# divchrono-aux.net
KiCad netlist of a schematic drawn in EAGLE
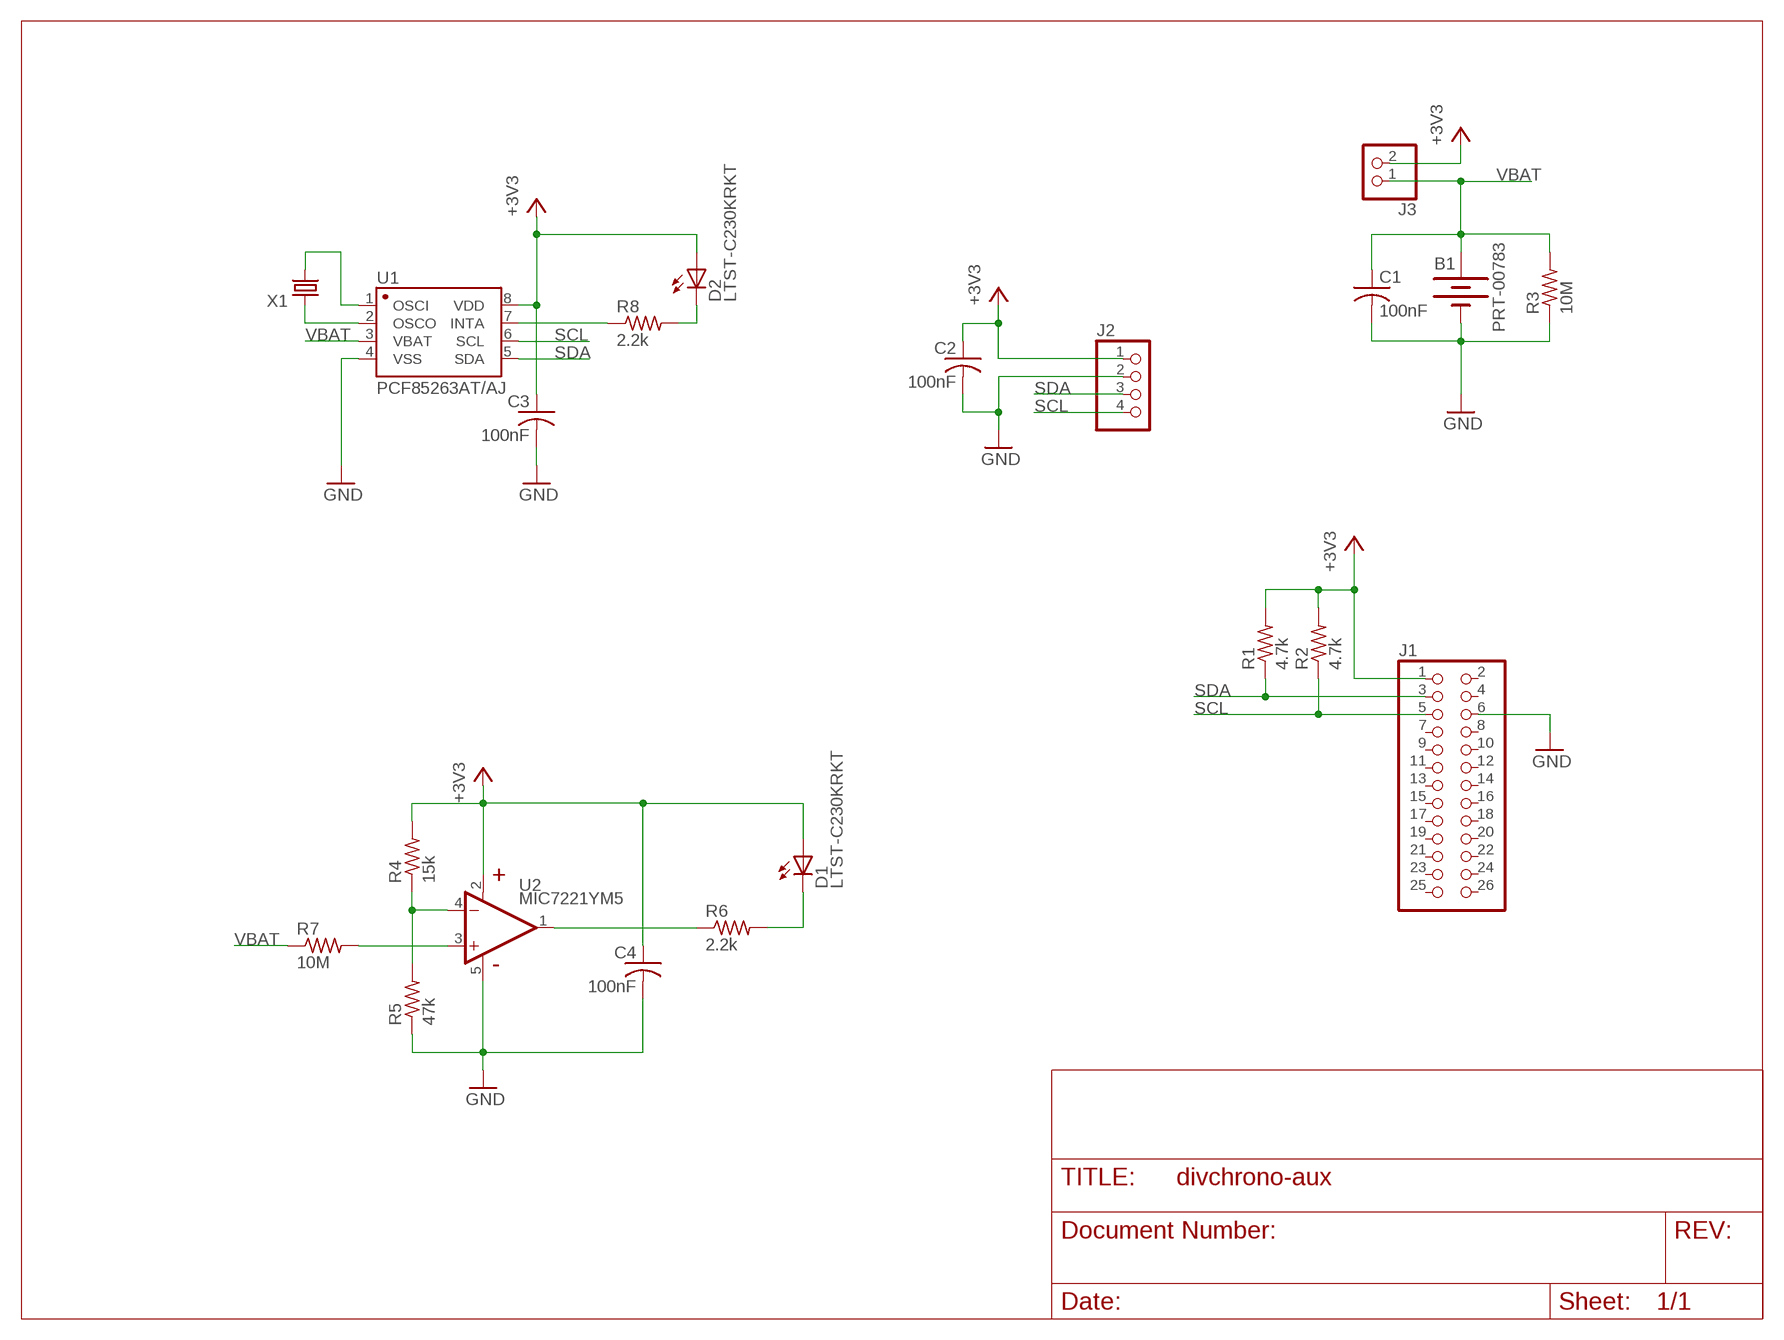
[diagram p0: schematic, sheet 1]

(export (version "E")
  (design (tool "Eeschema 10.0.6"))
  (components
    (comp (ref "B1")
      (value "PRT-00783")
      (footprint "eagle-import:BATTCOM_20MM_PTH")
      (libsource (lib "eagle-import") (part "BATTERY20PTH"))
    )
    (comp (ref "C1")
      (value "100nF")
      (footprint "eagle-import:C1206")
      (libsource (lib "eagle-import") (part "C-USC1206"))
    )
    (comp (ref "C2")
      (value "100nF")
      (footprint "eagle-import:C1206")
      (libsource (lib "eagle-import") (part "C-USC1206"))
    )
    (comp (ref "C3")
      (value "100nF")
      (footprint "eagle-import:C1206")
      (libsource (lib "eagle-import") (part "C-USC1206"))
    )
    (comp (ref "C4")
      (value "100nF")
      (footprint "eagle-import:C1206")
      (libsource (lib "eagle-import") (part "C-USC1206"))
    )
    (comp (ref "D1")
      (value "LTST-C230KRKT")
      (footprint "eagle-import:CHIPLED_1206")
      (libsource (lib "eagle-import") (part "LEDCHIPLED_1206"))
    )
    (comp (ref "D2")
      (value "LTST-C230KRKT")
      (footprint "eagle-import:CHIPLED_1206")
      (libsource (lib "eagle-import") (part "LEDCHIPLED_1206"))
    )
    (comp (ref "J1")
      (value "PINHD-2X13")
      (footprint "eagle-import:2X13")
      (libsource (lib "eagle-import") (part "PINHD-2X13"))
    )
    (comp (ref "J2")
      (value "PINHD-1X4")
      (footprint "eagle-import:1X04")
      (libsource (lib "eagle-import") (part "PINHD-1X4"))
    )
    (comp (ref "J3")
      (value "PINHD-1X2")
      (footprint "eagle-import:1X02")
      (libsource (lib "eagle-import") (part "PINHD-1X2"))
    )
    (comp (ref "R1")
      (value "4.7k")
      (footprint "eagle-import:R1206")
      (libsource (lib "eagle-import") (part "R-US_R1206"))
    )
    (comp (ref "R2")
      (value "4.7k")
      (footprint "eagle-import:R1206")
      (libsource (lib "eagle-import") (part "R-US_R1206"))
    )
    (comp (ref "R3")
      (value "10M")
      (footprint "eagle-import:R1206")
      (libsource (lib "eagle-import") (part "R-US_R1206"))
    )
    (comp (ref "R4")
      (value "15k")
      (footprint "eagle-import:R1206")
      (libsource (lib "eagle-import") (part "R-US_R1206"))
    )
    (comp (ref "R5")
      (value "47k")
      (footprint "eagle-import:R1206")
      (libsource (lib "eagle-import") (part "R-US_R1206"))
    )
    (comp (ref "R6")
      (value "2.2k")
      (footprint "eagle-import:R1206")
      (libsource (lib "eagle-import") (part "R-US_R1206"))
    )
    (comp (ref "R7")
      (value "10M")
      (footprint "eagle-import:R1206")
      (libsource (lib "eagle-import") (part "R-US_R1206"))
    )
    (comp (ref "R8")
      (value "2.2k")
      (footprint "eagle-import:R1206")
      (libsource (lib "eagle-import") (part "R-US_R1206"))
    )
    (comp (ref "U1")
      (value "PCF85263AT/AJ")
      (footprint "eagle-import:SOIC-8")
      (libsource (lib "eagle-import") (part "PCF85263"))
    )
    (comp (ref "U2")
      (value "MIC7221YM5")
      (footprint "eagle-import:SOT23-5")
      (libsource (lib "eagle-import") (part "MIC7221YM5"))
    )
    (comp (ref "X1")
      (value "CRYSTALS-NOGND-WATCH-3X8")
      (footprint "eagle-import:WATCH-3X8")
      (libsource (lib "eagle-import") (part "CRYSTALS-NOGND-WATCH-3X8"))
    )
  )
  (nets
    (net (code "1") (name "+3V3") (class "Default")
      (node (ref "C2") (pin "1") (pinfunction "1_1") (pintype "passive"))
      (node (ref "C3") (pin "1") (pinfunction "1_1") (pintype "passive"))
      (node (ref "C4") (pin "1") (pinfunction "1_1") (pintype "passive"))
      (node (ref "D1") (pin "A") (pinfunction "A_A") (pintype "passive"))
      (node (ref "D2") (pin "A") (pinfunction "A_A") (pintype "passive"))
      (node (ref "J1") (pin "1") (pinfunction "1_1") (pintype "passive"))
      (node (ref "J2") (pin "1") (pinfunction "1_1") (pintype "passive"))
      (node (ref "J3") (pin "2") (pinfunction "2_2") (pintype "passive"))
      (node (ref "R1") (pin "2") (pinfunction "2_2") (pintype "passive"))
      (node (ref "R2") (pin "2") (pinfunction "2_2") (pintype "passive"))
      (node (ref "R4") (pin "2") (pinfunction "2_2") (pintype "passive"))
      (node (ref "U1") (pin "8") (pinfunction "VDD_8") (pintype "power_in"))
      (node (ref "U2") (pin "2") (pinfunction "V+_2") (pintype "power_in"))
    )
    (net (code "2") (name "/SCL") (class "Default")
      (node (ref "J1") (pin "5") (pinfunction "5_5") (pintype "passive"))
      (node (ref "J2") (pin "4") (pinfunction "4_4") (pintype "passive"))
      (node (ref "R2") (pin "1") (pinfunction "1_1") (pintype "passive"))
      (node (ref "U1") (pin "6") (pinfunction "SCL_6") (pintype "bidirectional"))
    )
    (net (code "3") (name "/SDA") (class "Default")
      (node (ref "J1") (pin "3") (pinfunction "3_3") (pintype "passive"))
      (node (ref "J2") (pin "3") (pinfunction "3_3") (pintype "passive"))
      (node (ref "R1") (pin "1") (pinfunction "1_1") (pintype "passive"))
      (node (ref "U1") (pin "5") (pinfunction "SDA_5") (pintype "bidirectional"))
    )
    (net (code "4") (name "/VBAT") (class "Default")
      (node (ref "B1") (pin "1") (pinfunction "+_1") (pintype "power_in"))
      (node (ref "C1") (pin "1") (pinfunction "1_1") (pintype "passive"))
      (node (ref "J3") (pin "1") (pinfunction "1_1") (pintype "passive"))
      (node (ref "R3") (pin "2") (pinfunction "2_2") (pintype "passive"))
      (node (ref "R7") (pin "1") (pinfunction "1_1") (pintype "passive"))
      (node (ref "U1") (pin "3") (pinfunction "VBAT_3") (pintype "power_in"))
    )
    (net (code "5") (name "GND") (class "Default")
      (node (ref "B1") (pin "2") (pinfunction "-_2") (pintype "power_in"))
      (node (ref "C1") (pin "2") (pinfunction "2_2") (pintype "passive"))
      (node (ref "C2") (pin "2") (pinfunction "2_2") (pintype "passive"))
      (node (ref "C3") (pin "2") (pinfunction "2_2") (pintype "passive"))
      (node (ref "C4") (pin "2") (pinfunction "2_2") (pintype "passive"))
      (node (ref "J1") (pin "6") (pinfunction "6_6") (pintype "passive"))
      (node (ref "J2") (pin "2") (pinfunction "2_2") (pintype "passive"))
      (node (ref "R3") (pin "1") (pinfunction "1_1") (pintype "passive"))
      (node (ref "R5") (pin "1") (pinfunction "1_1") (pintype "passive"))
      (node (ref "U1") (pin "4") (pinfunction "VSS_4") (pintype "power_in"))
      (node (ref "U2") (pin "5") (pinfunction "V-_5") (pintype "power_in"))
    )
    (net (code "6") (name "Net-(D1-PadC)") (class "Default")
      (node (ref "D1") (pin "C") (pinfunction "C_C") (pintype "passive"))
      (node (ref "R6") (pin "2") (pinfunction "2_2") (pintype "passive"))
    )
    (net (code "7") (name "Net-(D2-PadC)") (class "Default")
      (node (ref "D2") (pin "C") (pinfunction "C_C") (pintype "passive"))
      (node (ref "R8") (pin "2") (pinfunction "2_2") (pintype "passive"))
    )
    (net (code "8") (name "Net-(U1-INTA)") (class "Default")
      (node (ref "R8") (pin "1") (pinfunction "1_1") (pintype "passive"))
      (node (ref "U1") (pin "7") (pinfunction "INTA_7") (pintype "bidirectional"))
    )
    (net (code "9") (name "Net-(U1-OSCI)") (class "Default")
      (node (ref "U1") (pin "1") (pinfunction "OSCI_1") (pintype "bidirectional"))
      (node (ref "X1") (pin "2") (pinfunction "2_2") (pintype "passive"))
    )
    (net (code "10") (name "Net-(U1-OSCO)") (class "Default")
      (node (ref "U1") (pin "2") (pinfunction "OSCO_2") (pintype "bidirectional"))
      (node (ref "X1") (pin "1") (pinfunction "1_1") (pintype "passive"))
    )
    (net (code "11") (name "Net-(U2-+IN)") (class "Default")
      (node (ref "R7") (pin "2") (pinfunction "2_2") (pintype "passive"))
      (node (ref "U2") (pin "3") (pinfunction "+IN_3") (pintype "input"))
    )
    (net (code "12") (name "Net-(U2--IN)") (class "Default")
      (node (ref "R4") (pin "1") (pinfunction "1_1") (pintype "passive"))
      (node (ref "R5") (pin "2") (pinfunction "2_2") (pintype "passive"))
      (node (ref "U2") (pin "4") (pinfunction "-IN_4") (pintype "input"))
    )
    (net (code "13") (name "Net-(U2-OUT)") (class "Default")
      (node (ref "R6") (pin "1") (pinfunction "1_1") (pintype "passive"))
      (node (ref "U2") (pin "1") (pinfunction "OUT_1") (pintype "output"))
    )
    (net (code "14") (name "unconnected-(J1-Pad2)") (class "Default")
      (node (ref "J1") (pin "2") (pinfunction "2_2") (pintype "passive"))
    )
    (net (code "15") (name "unconnected-(J1-Pad4)") (class "Default")
      (node (ref "J1") (pin "4") (pinfunction "4_4") (pintype "passive"))
    )
    (net (code "16") (name "unconnected-(J1-Pad7)") (class "Default")
      (node (ref "J1") (pin "7") (pinfunction "7_7") (pintype "passive"))
    )
    (net (code "17") (name "unconnected-(J1-Pad8)") (class "Default")
      (node (ref "J1") (pin "8") (pinfunction "8_8") (pintype "passive"))
    )
    (net (code "18") (name "unconnected-(J1-Pad9)") (class "Default")
      (node (ref "J1") (pin "9") (pinfunction "9_9") (pintype "passive"))
    )
    (net (code "19") (name "unconnected-(J1-Pad10)") (class "Default")
      (node (ref "J1") (pin "10") (pinfunction "10_10") (pintype "passive"))
    )
    (net (code "20") (name "unconnected-(J1-Pad11)") (class "Default")
      (node (ref "J1") (pin "11") (pinfunction "11_11") (pintype "passive"))
    )
    (net (code "21") (name "unconnected-(J1-Pad12)") (class "Default")
      (node (ref "J1") (pin "12") (pinfunction "12_12") (pintype "passive"))
    )
    (net (code "22") (name "unconnected-(J1-Pad13)") (class "Default")
      (node (ref "J1") (pin "13") (pinfunction "13_13") (pintype "passive"))
    )
    (net (code "23") (name "unconnected-(J1-Pad14)") (class "Default")
      (node (ref "J1") (pin "14") (pinfunction "14_14") (pintype "passive"))
    )
    (net (code "24") (name "unconnected-(J1-Pad15)") (class "Default")
      (node (ref "J1") (pin "15") (pinfunction "15_15") (pintype "passive"))
    )
    (net (code "25") (name "unconnected-(J1-Pad16)") (class "Default")
      (node (ref "J1") (pin "16") (pinfunction "16_16") (pintype "passive"))
    )
    (net (code "26") (name "unconnected-(J1-Pad17)") (class "Default")
      (node (ref "J1") (pin "17") (pinfunction "17_17") (pintype "passive"))
    )
    (net (code "27") (name "unconnected-(J1-Pad18)") (class "Default")
      (node (ref "J1") (pin "18") (pinfunction "18_18") (pintype "passive"))
    )
    (net (code "28") (name "unconnected-(J1-Pad19)") (class "Default")
      (node (ref "J1") (pin "19") (pinfunction "19_19") (pintype "passive"))
    )
    (net (code "29") (name "unconnected-(J1-Pad20)") (class "Default")
      (node (ref "J1") (pin "20") (pinfunction "20_20") (pintype "passive"))
    )
    (net (code "30") (name "unconnected-(J1-Pad21)") (class "Default")
      (node (ref "J1") (pin "21") (pinfunction "21_21") (pintype "passive"))
    )
    (net (code "31") (name "unconnected-(J1-Pad22)") (class "Default")
      (node (ref "J1") (pin "22") (pinfunction "22_22") (pintype "passive"))
    )
    (net (code "32") (name "unconnected-(J1-Pad23)") (class "Default")
      (node (ref "J1") (pin "23") (pinfunction "23_23") (pintype "passive"))
    )
    (net (code "33") (name "unconnected-(J1-Pad24)") (class "Default")
      (node (ref "J1") (pin "24") (pinfunction "24_24") (pintype "passive"))
    )
    (net (code "34") (name "unconnected-(J1-Pad25)") (class "Default")
      (node (ref "J1") (pin "25") (pinfunction "25_25") (pintype "passive"))
    )
    (net (code "35") (name "unconnected-(J1-Pad26)") (class "Default")
      (node (ref "J1") (pin "26") (pinfunction "26_26") (pintype "passive"))
    )
  )
)
